# FanController.net
KiCad netlist of a schematic drawn in Altium Designer
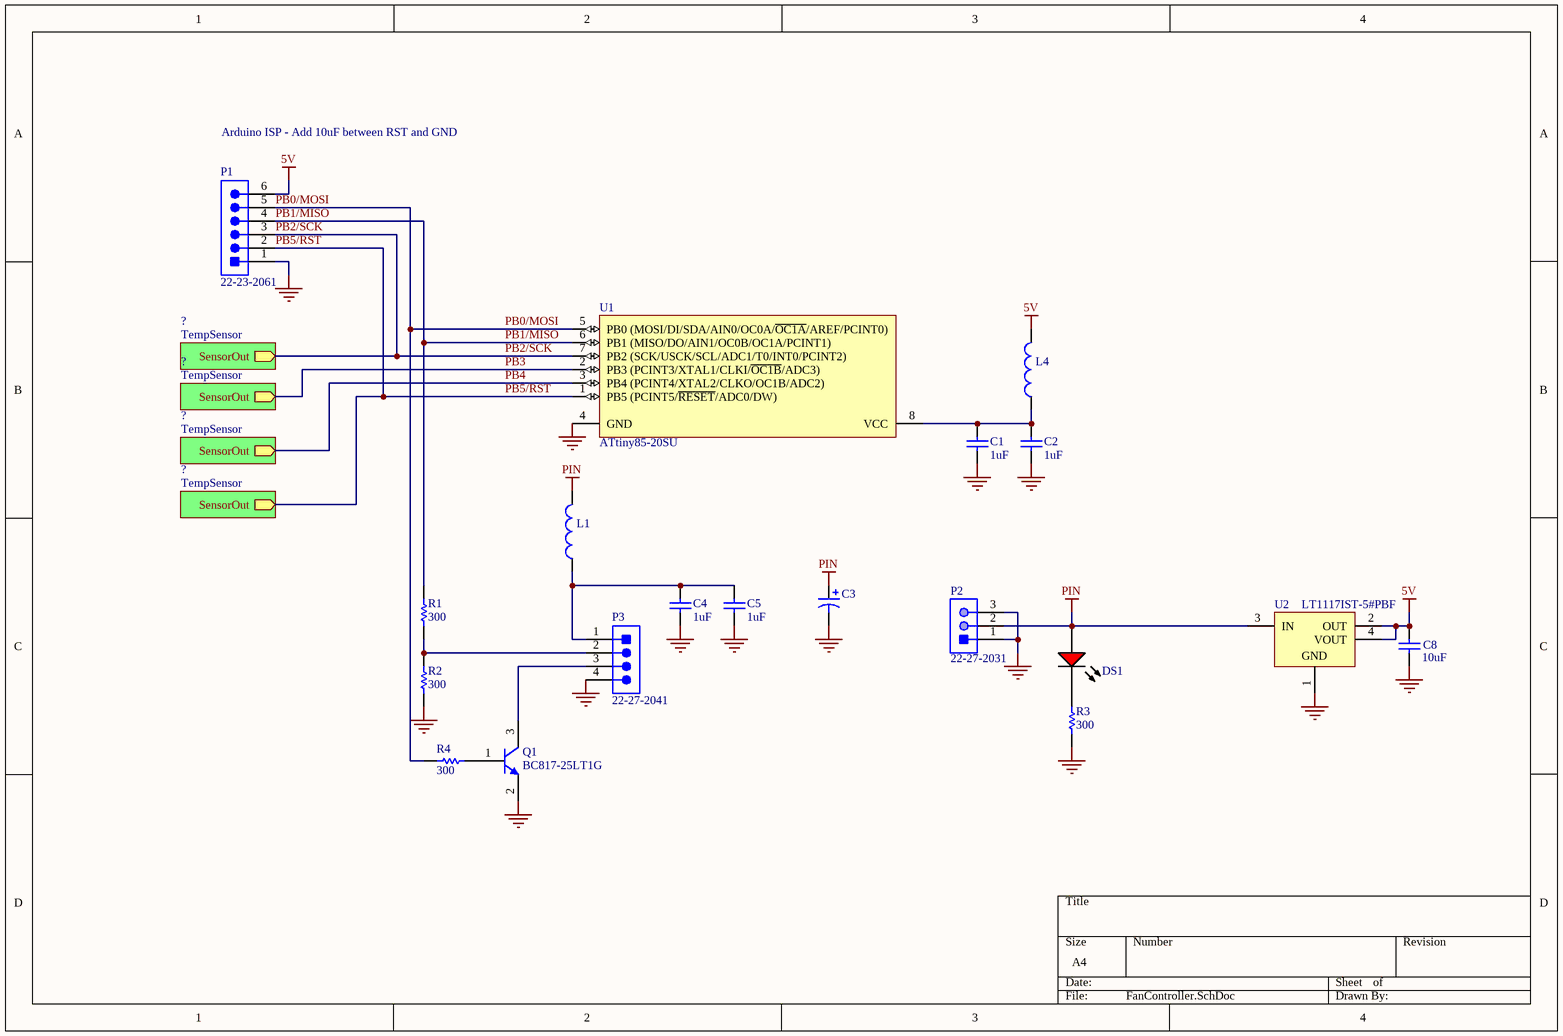
[diagram p0: FanController.SchDoc]

(export (version "E")
  (design (tool "Eeschema 10.0.6"))
  (components
    (comp (ref "C1")
      (value "1uF")
      (footprint "CAPC0805(2012)145_N")
      (fields (field (name "TOLERANCE") "Â±20%"))
      (libsource (lib "Altium Content Vault") (part "CAP"))
    )
    (comp (ref "C2")
      (value "1uF")
      (footprint "CAPC0805(2012)145_N")
      (fields (field (name "TOLERANCE") "Â±20%"))
      (libsource (lib "Altium Content Vault") (part "CAP"))
    )
    (comp (ref "C3")
      (value "ECA-1JHG471")
      (footprint "PNSC-ECA-1JHG471")
      (description "CAP ALUM 470UF 63V 20% RADIAL")
      (fields (field (name "MANUFACTURER") "Panasonic"))
      (libsource (lib "Altium Content Vault") (part "CAP-P-2"))
    )
    (comp (ref "C4")
      (value "1uF")
      (footprint "CAPC0805(2012)145_N")
      (fields (field (name "TOLERANCE") "Â±20%"))
      (libsource (lib "Altium Content Vault") (part "CAP"))
    )
    (comp (ref "C5")
      (value "1uF")
      (footprint "CAPC0805(2012)145_N")
      (fields (field (name "TOLERANCE") "Â±20%"))
      (libsource (lib "Altium Content Vault") (part "CAP"))
    )
    (comp (ref "C8")
      (value "10uF")
      (footprint "CAPC1206(3216)130_L")
      (description "CAP 10uF 10V -20% to +80% 1206 (3216 Metric) Thickness 1.3mm SMD")
      (fields (field (name "TOLERANCE") "-20% to +80%"))
      (libsource (lib "Altium Content Vault") (part "CAP"))
    )
    (comp (ref "DS1")
      (value "TLMS1100-GS08")
      (footprint "VISH-TLMX1100_V")
      (description "LED, RED, 2.1 V, -40 to 100 degC, 2-Pin SMD (0603), RoHS, Tape and Reel")
      (fields (field (name "TOLERANCE") "5%"))
      (libsource (lib "Altium Content Vault") (part "LED-RED-AK-2"))
    )
    (comp (ref "L1")
      (value "FBMJ2125HM210NT")
      (footprint "INDC2013X105X50LL20T30")
      (description "Chip Inductor, 21 Ohm, +/- 30%, 6 A, -40 to 125 degC, 0805 (2012 Metric), RoHS, Tape and Reel")
      (fields (field (name "TOLERANCE") "30%"))
      (libsource (lib "Altium Content Vault") (part "IND-2"))
    )
    (comp (ref "L4")
      (value "FBMJ2125HM210NT")
      (footprint "INDC2013X105X50LL20T30")
      (description "Chip Inductor, 21 Ohm, +/- 30%, 6 A, -40 to 125 degC, 0805 (2012 Metric), RoHS, Tape and Reel")
      (fields (field (name "TOLERANCE") "30%"))
      (libsource (lib "Altium Content Vault") (part "IND-2"))
    )
    (comp (ref "P1")
      (value "22-23-2061")
      (footprint "MOLX-22-23-2061_V")
      (fields (field (name "MANUFACTURER") "Molex"))
      (libsource (lib "Altium Content Vault") (part "CN-1P-M-R6"))
    )
    (comp (ref "P2")
      (value "22-27-2031")
      (footprint "MOLX-22-27-2031_V")
      (fields (field (name "MANUFACTURER") "Molex"))
      (libsource (lib "Altium Content Vault") (part "CN-1P-M-R3"))
    )
    (comp (ref "P3")
      (value "22-27-2041")
      (footprint "MOLX-22-27-2041_V")
      (description "Male Header, Pitch 2.54 mm, 1 x 4 Position, Height 11.7 mm, Tail Length 3.56 mm, RoHS, Bulk")
      (fields (field (name "MANUFACTURER") "Molex"))
      (libsource (lib "Altium Content Vault") (part "CN-1P-M-R4"))
    )
    (comp (ref "Q1")
      (value "BC817-25LT1G")
      (footprint "ONSC-SOT-23-3-318-08_V")
      (description "General Purpose Transistor, NPN Silicon, 3-Pin SOT-23, Pb-Free, Tape and Reel")
      (fields (field (name "MANUFACTURER") "On Semiconductor"))
      (libsource (lib "Altium Content Vault") (part "ONSC-NPN-B1E2C3-3"))
    )
    (comp (ref "R1")
      (value "300")
      (footprint "RESC0805(2012)_M")
      (description "300R 0.125W 1% 0805 (2012 Metric)  SMD")
      (fields (field (name "TOLERANCE") "1 %") (field (name "POWER") "0.125 W"))
      (libsource (lib "Altium Content Vault") (part "RES"))
    )
    (comp (ref "R2")
      (value "300")
      (footprint "RESC0805(2012)_M")
      (description "300R 0.125W 1% 0805 (2012 Metric)  SMD")
      (fields (field (name "TOLERANCE") "1 %") (field (name "POWER") "0.125 W"))
      (libsource (lib "Altium Content Vault") (part "RES"))
    )
    (comp (ref "R3")
      (value "300")
      (footprint "RESC0805(2012)_M")
      (description "300R 0.125W 1% 0805 (2012 Metric)  SMD")
      (fields (field (name "TOLERANCE") "1 %") (field (name "POWER") "0.125 W"))
      (libsource (lib "Altium Content Vault") (part "RES"))
    )
    (comp (ref "R4")
      (value "300")
      (footprint "RESC0805(2012)_M")
      (description "300R 0.125W 1% 0805 (2012 Metric)  SMD")
      (fields (field (name "TOLERANCE") "1 %") (field (name "POWER") "0.125 W"))
      (libsource (lib "Altium Content Vault") (part "RES"))
    )
    (comp (ref "U1")
      (value "ATtiny85-20SU")
      (footprint "8S2_M")
      (libsource (lib "Altium Content Vault") (part "MC-8B-ATT25-IL8"))
    )
    (comp (ref "U2")
      (value "LT1117IST-5#PBF")
      (footprint "LT-ST-3-SOT-223_L")
      (fields (field (name "MANUFACTURER") "Linear Technology"))
      (libsource (lib "Altium Content Vault") (part "LT-LT1117-3_B"))
    )
  )
  (nets
    (net (code "1") (name "/PB0{slash}MOSI") (class "Default")
      (node (ref "P1") (pin "5") (pinfunction "5_5") (pintype "passive"))
      (node (ref "R4") (pin "1") (pinfunction "1_1") (pintype "passive"))
      (node (ref "U1") (pin "5") (pinfunction "PB0_(MOSI/DI/SDA/AIN0/OC0A/~{OC1A}/AREF/PCINT0)_5") (pintype "bidirectional"))
    )
    (net (code "2") (name "/PB1{slash}MISO") (class "Default")
      (node (ref "P1") (pin "4") (pinfunction "4_4") (pintype "passive"))
      (node (ref "R1") (pin "2") (pinfunction "2_2") (pintype "passive"))
      (node (ref "U1") (pin "6") (pinfunction "PB1_(MISO/DO/AIN1/OC0B/OC1A/PCINT1)_6") (pintype "bidirectional"))
    )
    (net (code "3") (name "/PB2{slash}SCK") (class "Default")
      (node (ref "P1") (pin "3") (pinfunction "3_3") (pintype "passive"))
      (node (ref "U1") (pin "7") (pinfunction "PB2_(SCK/USCK/SCL/ADC1/T0/INT0/PCINT2)_7") (pintype "bidirectional"))
    )
    (net (code "4") (name "/PB3") (class "Default")
      (node (ref "U1") (pin "2") (pinfunction "PB3_(PCINT3/XTAL1/CLKI/~{OC1B}/ADC3)_2") (pintype "bidirectional"))
    )
    (net (code "5") (name "/PB4") (class "Default")
      (node (ref "U1") (pin "3") (pinfunction "PB4_(PCINT4/XTAL2/CLKO/OC1B/ADC2)_3") (pintype "bidirectional"))
    )
    (net (code "6") (name "/PB5{slash}RST") (class "Default")
      (node (ref "P1") (pin "2") (pinfunction "2_2") (pintype "passive"))
      (node (ref "U1") (pin "1") (pinfunction "PB5_(PCINT5/~{RESET}/ADC0/DW)_1") (pintype "bidirectional"))
    )
    (net (code "7") (name "5V") (class "Default")
      (node (ref "C8") (pin "2") (pinfunction "2_2") (pintype "passive"))
      (node (ref "L4") (pin "2") (pinfunction "2_2") (pintype "passive"))
      (node (ref "P1") (pin "6") (pinfunction "6_6") (pintype "passive"))
      (node (ref "U2") (pin "2") (pinfunction "OUT_2") (pintype "power_in"))
      (node (ref "U2") (pin "4") (pinfunction "VOUT_4") (pintype "power_in"))
    )
    (net (code "8") (name "GND") (class "Default")
      (node (ref "C1") (pin "1") (pinfunction "1_1") (pintype "passive"))
      (node (ref "C2") (pin "1") (pinfunction "1_1") (pintype "passive"))
      (node (ref "C3") (pin "2") (pinfunction "-_2") (pintype "passive"))
      (node (ref "C4") (pin "1") (pinfunction "1_1") (pintype "passive"))
      (node (ref "C5") (pin "1") (pinfunction "1_1") (pintype "passive"))
      (node (ref "C8") (pin "1") (pinfunction "1_1") (pintype "passive"))
      (node (ref "P1") (pin "1") (pinfunction "1_1") (pintype "passive"))
      (node (ref "P2") (pin "1") (pinfunction "1_1") (pintype "passive"))
      (node (ref "P2") (pin "3") (pinfunction "3_3") (pintype "passive"))
      (node (ref "P3") (pin "4") (pinfunction "4_4") (pintype "passive"))
      (node (ref "Q1") (pin "2") (pinfunction "E_2") (pintype "passive"))
      (node (ref "R2") (pin "1") (pinfunction "1_1") (pintype "passive"))
      (node (ref "R3") (pin "1") (pinfunction "1_1") (pintype "passive"))
      (node (ref "U1") (pin "4") (pinfunction "GND_4") (pintype "power_in"))
      (node (ref "U2") (pin "1") (pinfunction "GND_1") (pintype "power_in"))
    )
    (net (code "9") (name "Net-(C4-Pad2)") (class "Default")
      (node (ref "C4") (pin "2") (pinfunction "2_2") (pintype "passive"))
      (node (ref "C5") (pin "2") (pinfunction "2_2") (pintype "passive"))
      (node (ref "L1") (pin "1") (pinfunction "1_1") (pintype "passive"))
      (node (ref "P3") (pin "1") (pinfunction "1_1") (pintype "passive"))
    )
    (net (code "10") (name "Net-(DS1-K)") (class "Default")
      (node (ref "DS1") (pin "2") (pinfunction "K_2") (pintype "passive"))
      (node (ref "R3") (pin "2") (pinfunction "2_2") (pintype "passive"))
    )
    (net (code "11") (name "Net-(P3-Pad2)") (class "Default")
      (node (ref "P3") (pin "2") (pinfunction "2_2") (pintype "passive"))
      (node (ref "R1") (pin "1") (pinfunction "1_1") (pintype "passive"))
      (node (ref "R2") (pin "2") (pinfunction "2_2") (pintype "passive"))
    )
    (net (code "12") (name "Net-(Q1-B)") (class "Default")
      (node (ref "Q1") (pin "1") (pinfunction "B_1") (pintype "passive"))
      (node (ref "R4") (pin "2") (pinfunction "2_2") (pintype "passive"))
    )
    (net (code "13") (name "Net-(Q1-C)") (class "Default")
      (node (ref "P3") (pin "3") (pinfunction "3_3") (pintype "passive"))
      (node (ref "Q1") (pin "3") (pinfunction "C_3") (pintype "passive"))
    )
    (net (code "14") (name "Net-(U1-VCC)") (class "Default")
      (node (ref "C1") (pin "2") (pinfunction "2_2") (pintype "passive"))
      (node (ref "C2") (pin "2") (pinfunction "2_2") (pintype "passive"))
      (node (ref "L4") (pin "1") (pinfunction "1_1") (pintype "passive"))
      (node (ref "U1") (pin "8") (pinfunction "VCC_8") (pintype "power_in"))
    )
    (net (code "15") (name "PIN") (class "Default")
      (node (ref "C3") (pin "1") (pinfunction "+_1") (pintype "passive"))
      (node (ref "DS1") (pin "1") (pinfunction "A_1") (pintype "passive"))
      (node (ref "L1") (pin "2") (pinfunction "2_2") (pintype "passive"))
      (node (ref "P2") (pin "2") (pinfunction "2_2") (pintype "passive"))
      (node (ref "U2") (pin "3") (pinfunction "IN_3") (pintype "power_in"))
    )
  )
)
